# MCU.net
KiCad netlist of a schematic drawn in Altium Designer
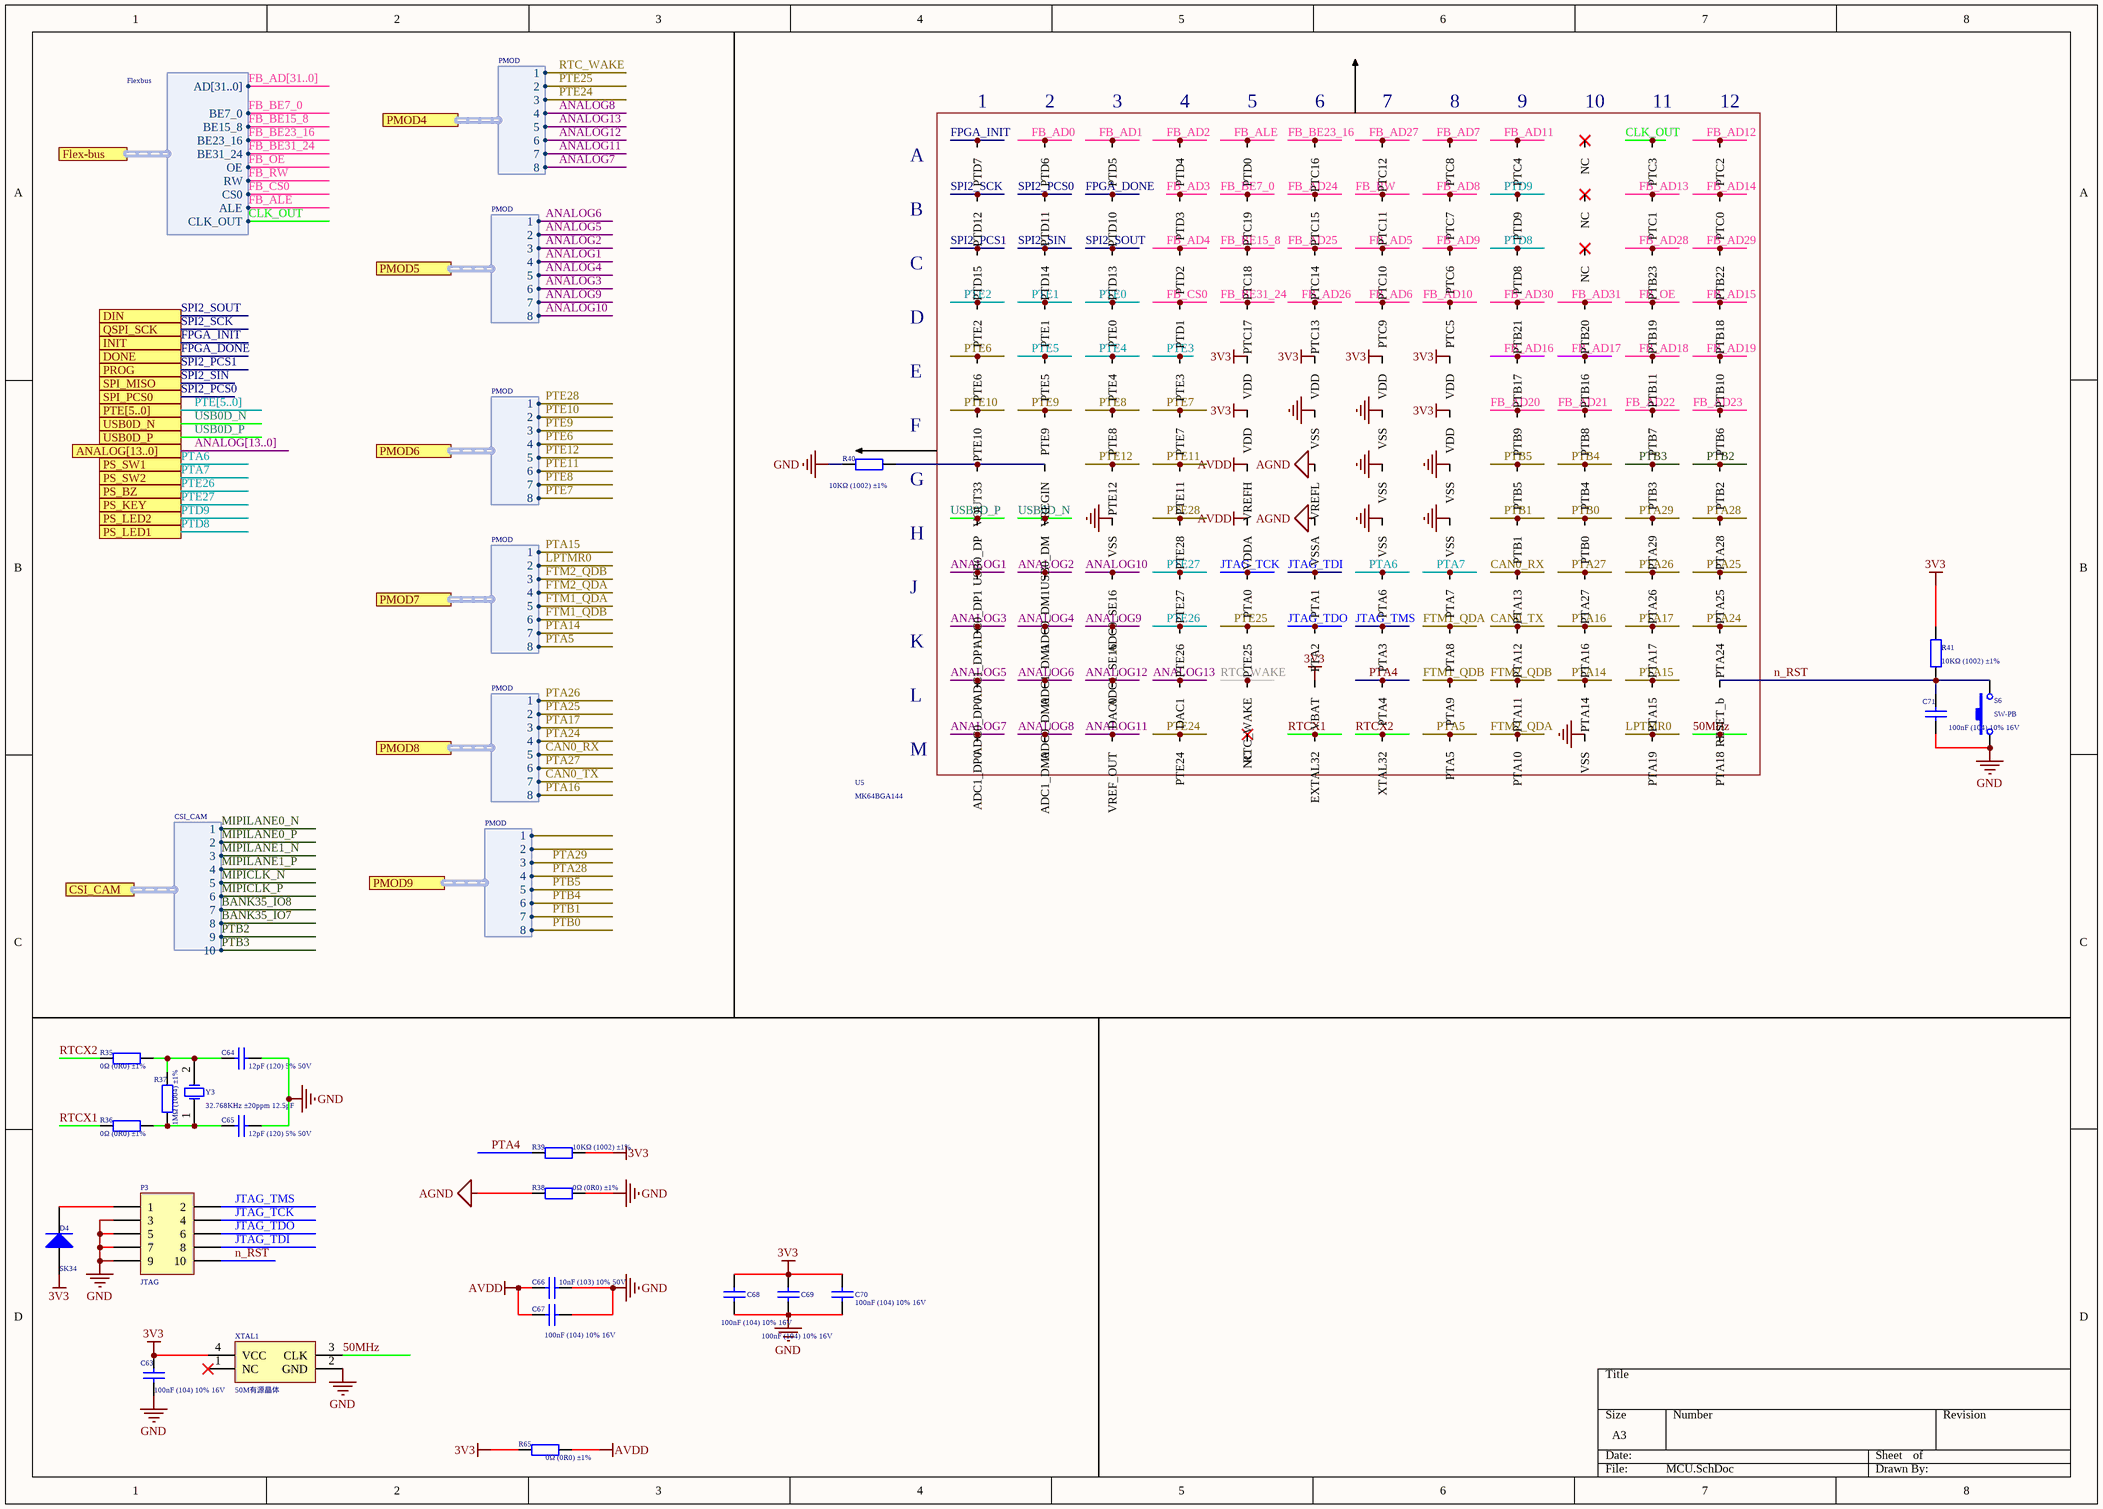
[diagram p0: MCU.SchDoc]

(export (version "E")
  (design (tool "Eeschema 10.0.6"))
  (components
    (comp (ref "C63")
      (value "100nF (104) 10% 16V")
      (footprint "0402_C")
      (description "贴片电容")
      (libsource (lib "Cap") (part "0402 100nF (104) 10% 16V"))
    )
    (comp (ref "C64")
      (value "12pF (120) 5% 50V")
      (footprint "0402_C")
      (description "贴片电容")
      (libsource (lib "Cap") (part "0402 12pF (120) 5% 50V"))
    )
    (comp (ref "C65")
      (value "12pF (120) 5% 50V")
      (footprint "0402_C")
      (description "贴片电容")
      (libsource (lib "Cap") (part "0402 12pF (120) 5% 50V"))
    )
    (comp (ref "C66")
      (value "10nF (103) 10% 50V")
      (footprint "0402_C")
      (description "贴片电容")
      (libsource (lib "Cap") (part "0402 10nF (103) 10% 50V"))
    )
    (comp (ref "C67")
      (value "100nF (104) 10% 16V")
      (footprint "0402_C")
      (description "贴片电容")
      (libsource (lib "Cap") (part "0402 100nF (104) 10% 16V"))
    )
    (comp (ref "C68")
      (value "100nF (104) 10% 16V")
      (footprint "0402_C")
      (description "贴片电容")
      (libsource (lib "Cap") (part "0402 100nF (104) 10% 16V"))
    )
    (comp (ref "C69")
      (value "100nF (104) 10% 16V")
      (footprint "0402_C")
      (description "贴片电容")
      (libsource (lib "Cap") (part "0402 100nF (104) 10% 16V"))
    )
    (comp (ref "C70")
      (value "100nF (104) 10% 16V")
      (footprint "0402_C")
      (description "贴片电容")
      (libsource (lib "Cap") (part "0402 100nF (104) 10% 16V"))
    )
    (comp (ref "C71")
      (value "100nF (104) 10% 16V")
      (footprint "0402_C")
      (description "贴片电容")
      (libsource (lib "Cap") (part "0402 100nF (104) 10% 16V"))
    )
    (comp (ref "D4")
      (value "SK34")
      (footprint "C2012")
      (description "High Conductance Fast Diode")
      (fields (field (name "PUBLISHER") "Altium Limited"))
      (libsource (lib "K60-V4.0") (part "Diode 1N4148"))
    )
    (comp (ref "P3")
      (value "JTAG")
      (footprint "HDR2X5")
      (description "Header, 5-Pin, Dual row")
      (fields (field (name "PUBLISHER") "Altium Limited"))
      (libsource (lib "Sparks") (part "Header 5X2"))
    )
    (comp (ref "R35")
      (value "0Ω (0R0) ±1%")
      (footprint "0402_R")
      (description "贴片电阻")
      (libsource (lib "RES") (part "0402 0Ω (0R0) 1%"))
    )
    (comp (ref "R36")
      (value "0Ω (0R0) ±1%")
      (footprint "0402_R")
      (description "贴片电阻")
      (libsource (lib "RES") (part "0402 0Ω (0R0) 1%"))
    )
    (comp (ref "R37")
      (value "1MΩ (1004) ±1%")
      (footprint "0402_R")
      (description "贴片电阻")
      (libsource (lib "RES") (part "0402 1MΩ (1004) 1%"))
    )
    (comp (ref "R38")
      (value "0Ω (0R0) ±1%")
      (footprint "0402_R")
      (description "贴片电阻")
      (libsource (lib "RES") (part "0402 0Ω (0R0) 1%"))
    )
    (comp (ref "R39")
      (value "10KΩ (1002) ±1%")
      (footprint "0402_R")
      (description "贴片电阻")
      (libsource (lib "") (part "0402 10KΩ (1002) 1%_1"))
    )
    (comp (ref "R40")
      (value "10KΩ (1002) ±1%")
      (footprint "0402_R")
      (description "贴片电阻")
      (libsource (lib "") (part "0402 10KΩ (1002) 1%_1"))
    )
    (comp (ref "R41")
      (value "10KΩ (1002) ±1%")
      (footprint "0402_R")
      (description "贴片电阻")
      (libsource (lib "RES") (part "0402 10KΩ (1002) 1%"))
    )
    (comp (ref "R65")
      (value "0Ω (0R0) ±1%")
      (footprint "0402_R")
      (description "贴片电阻")
      (libsource (lib "Miscellaneous Devices LC") (part "0402 0Ω (0R0) 1%"))
    )
    (comp (ref "S6")
      (value "SW-PB")
      (footprint "key 3*4*2")
      (description "Switch")
      (libsource (lib "K60-V4.0") (part "SW-PB"))
    )
    (comp (ref "U5")
      (value "MK64BGA144")
      (footprint "BGA144C100P12X12_1300X1300X161")
      (libsource (lib "2号库") (part "MK64BGA144"))
    )
    (comp (ref "XTAL1") (value "50M有源晶体") (footprint "XTAL7_3225") (libsource (lib "Sparks") (part "有源晶体")))
    (comp (ref "Y3")
      (value "32.768KHz ±20ppm 12.5pF")
      (footprint "SMD-3215_2P FC - 135")
      (description "贴片晶振")
      (libsource (lib "CrystalOscillator") (part "SMD-3215_2P 32.768KHz 20ppm 12.5pF"))
    )
  )
  (nets
    (net (code "5") (name "/50MHz") (class "Default")
      (node (ref "U5") (pin "M12") (pinfunction "PTA18_M12") (pintype "passive"))
      (node (ref "XTAL1") (pin "3") (pinfunction "CLK_3") (pintype "passive"))
    )
    (net (code "6") (name "/ANALOG1") (class "Default")
      (node (ref "U5") (pin "J1") (pinfunction "ADC0_DP1_J1") (pintype "passive"))
    )
    (net (code "7") (name "/ANALOG2") (class "Default")
      (node (ref "U5") (pin "J2") (pinfunction "ADC0_DM1_J2") (pintype "passive"))
    )
    (net (code "8") (name "/ANALOG3") (class "Default")
      (node (ref "U5") (pin "K1") (pinfunction "ADC1_DP1_K1") (pintype "passive"))
    )
    (net (code "9") (name "/ANALOG4") (class "Default")
      (node (ref "U5") (pin "K2") (pinfunction "ADC1_DM1_K2") (pintype "passive"))
    )
    (net (code "10") (name "/ANALOG5") (class "Default")
      (node (ref "U5") (pin "L1") (pinfunction "ADC0_DP0_L1") (pintype "passive"))
    )
    (net (code "11") (name "/ANALOG6") (class "Default")
      (node (ref "U5") (pin "L2") (pinfunction "ADC0_DM0_L2") (pintype "passive"))
    )
    (net (code "12") (name "/ANALOG7") (class "Default")
      (node (ref "U5") (pin "M1") (pinfunction "ADC1_DP0_M1") (pintype "passive"))
    )
    (net (code "13") (name "/ANALOG8") (class "Default")
      (node (ref "U5") (pin "M2") (pinfunction "ADC1_DM0_M2") (pintype "passive"))
    )
    (net (code "14") (name "/ANALOG9") (class "Default")
      (node (ref "U5") (pin "K3") (pinfunction "ADC1_SE16_K3") (pintype "passive"))
    )
    (net (code "15") (name "/ANALOG10") (class "Default")
      (node (ref "U5") (pin "J3") (pinfunction "ADC0_SE16_J3") (pintype "passive"))
    )
    (net (code "16") (name "/ANALOG11") (class "Default")
      (node (ref "U5") (pin "M3") (pinfunction "VREF_OUT_M3") (pintype "passive"))
    )
    (net (code "17") (name "/ANALOG12") (class "Default")
      (node (ref "U5") (pin "L3") (pinfunction "DAC0_L3") (pintype "passive"))
    )
    (net (code "18") (name "/ANALOG13") (class "Default")
      (node (ref "U5") (pin "L4") (pinfunction "DAC1_L4") (pintype "passive"))
    )
    (net (code "22") (name "/CAN0_RX") (class "Default")
      (node (ref "U5") (pin "J9") (pinfunction "PTA13_J9") (pintype "passive"))
    )
    (net (code "23") (name "/CAN0_TX") (class "Default")
      (node (ref "U5") (pin "K9") (pinfunction "PTA12_K9") (pintype "passive"))
    )
    (net (code "24") (name "/CLK_OUT") (class "Default")
      (node (ref "U5") (pin "A11") (pinfunction "PTC3_A11") (pintype "passive"))
    )
    (net (code "25") (name "/FB_AD0") (class "Default")
      (node (ref "U5") (pin "A2") (pinfunction "PTD6_A2") (pintype "passive"))
    )
    (net (code "26") (name "/FB_AD1") (class "Default")
      (node (ref "U5") (pin "A3") (pinfunction "PTD5_A3") (pintype "passive"))
    )
    (net (code "27") (name "/FB_AD2") (class "Default")
      (node (ref "U5") (pin "A4") (pinfunction "PTD4_A4") (pintype "passive"))
    )
    (net (code "28") (name "/FB_AD3") (class "Default")
      (node (ref "U5") (pin "B4") (pinfunction "PTD3_B4") (pintype "passive"))
    )
    (net (code "29") (name "/FB_AD4") (class "Default")
      (node (ref "U5") (pin "C4") (pinfunction "PTD2_C4") (pintype "passive"))
    )
    (net (code "30") (name "/FB_AD5") (class "Default")
      (node (ref "U5") (pin "C7") (pinfunction "PTC10_C7") (pintype "passive"))
    )
    (net (code "31") (name "/FB_AD6") (class "Default")
      (node (ref "U5") (pin "D7") (pinfunction "PTC9_D7") (pintype "passive"))
    )
    (net (code "32") (name "/FB_AD7") (class "Default")
      (node (ref "U5") (pin "A8") (pinfunction "PTC8_A8") (pintype "passive"))
    )
    (net (code "33") (name "/FB_AD8") (class "Default")
      (node (ref "U5") (pin "B8") (pinfunction "PTC7_B8") (pintype "passive"))
    )
    (net (code "34") (name "/FB_AD9") (class "Default")
      (node (ref "U5") (pin "C8") (pinfunction "PTC6_C8") (pintype "passive"))
    )
    (net (code "35") (name "/FB_AD10") (class "Default")
      (node (ref "U5") (pin "D8") (pinfunction "PTC5_D8") (pintype "passive"))
    )
    (net (code "36") (name "/FB_AD11") (class "Default")
      (node (ref "U5") (pin "A9") (pinfunction "PTC4_A9") (pintype "passive"))
    )
    (net (code "37") (name "/FB_AD12") (class "Default")
      (node (ref "U5") (pin "A12") (pinfunction "PTC2_A12") (pintype "passive"))
    )
    (net (code "38") (name "/FB_AD13") (class "Default")
      (node (ref "U5") (pin "B11") (pinfunction "PTC1_B11") (pintype "passive"))
    )
    (net (code "39") (name "/FB_AD14") (class "Default")
      (node (ref "U5") (pin "B12") (pinfunction "PTC0_B12") (pintype "passive"))
    )
    (net (code "40") (name "/FB_AD15") (class "Default")
      (node (ref "U5") (pin "D12") (pinfunction "PTB18_D12") (pintype "passive"))
    )
    (net (code "41") (name "/FB_AD16") (class "Default")
      (node (ref "U5") (pin "E9") (pinfunction "PTB17_E9") (pintype "passive"))
    )
    (net (code "42") (name "/FB_AD17") (class "Default")
      (node (ref "U5") (pin "E10") (pinfunction "PTB16_E10") (pintype "passive"))
    )
    (net (code "43") (name "/FB_AD18") (class "Default")
      (node (ref "U5") (pin "E11") (pinfunction "PTB11_E11") (pintype "passive"))
    )
    (net (code "44") (name "/FB_AD19") (class "Default")
      (node (ref "U5") (pin "E12") (pinfunction "PTB10_E12") (pintype "passive"))
    )
    (net (code "45") (name "/FB_AD20") (class "Default")
      (node (ref "U5") (pin "F9") (pinfunction "PTB9_F9") (pintype "passive"))
    )
    (net (code "46") (name "/FB_AD21") (class "Default")
      (node (ref "U5") (pin "F10") (pinfunction "PTB8_F10") (pintype "passive"))
    )
    (net (code "47") (name "/FB_AD22") (class "Default")
      (node (ref "U5") (pin "F11") (pinfunction "PTB7_F11") (pintype "passive"))
    )
    (net (code "48") (name "/FB_AD23") (class "Default")
      (node (ref "U5") (pin "F12") (pinfunction "PTB6_F12") (pintype "passive"))
    )
    (net (code "49") (name "/FB_AD24") (class "Default")
      (node (ref "U5") (pin "B6") (pinfunction "PTC15_B6") (pintype "passive"))
    )
    (net (code "50") (name "/FB_AD25") (class "Default")
      (node (ref "U5") (pin "C6") (pinfunction "PTC14_C6") (pintype "passive"))
    )
    (net (code "51") (name "/FB_AD26") (class "Default")
      (node (ref "U5") (pin "D6") (pinfunction "PTC13_D6") (pintype "passive"))
    )
    (net (code "52") (name "/FB_AD27") (class "Default")
      (node (ref "U5") (pin "A7") (pinfunction "PTC12_A7") (pintype "passive"))
    )
    (net (code "53") (name "/FB_AD28") (class "Default")
      (node (ref "U5") (pin "C11") (pinfunction "PTB23_C11") (pintype "passive"))
    )
    (net (code "54") (name "/FB_AD29") (class "Default")
      (node (ref "U5") (pin "C12") (pinfunction "PTB22_C12") (pintype "passive"))
    )
    (net (code "55") (name "/FB_AD30") (class "Default")
      (node (ref "U5") (pin "D9") (pinfunction "PTB21_D9") (pintype "passive"))
    )
    (net (code "56") (name "/FB_AD31") (class "Default")
      (node (ref "U5") (pin "D10") (pinfunction "PTB20_D10") (pintype "passive"))
    )
    (net (code "58") (name "/FB_ALE") (class "Default")
      (node (ref "U5") (pin "A5") (pinfunction "PTD0_A5") (pintype "passive"))
    )
    (net (code "59") (name "/FB_BE7_0") (class "Default")
      (node (ref "U5") (pin "B5") (pinfunction "PTC19_B5") (pintype "passive"))
    )
    (net (code "60") (name "/FB_BE15_8") (class "Default")
      (node (ref "U5") (pin "C5") (pinfunction "PTC18_C5") (pintype "passive"))
    )
    (net (code "61") (name "/FB_BE23_16") (class "Default")
      (node (ref "U5") (pin "A6") (pinfunction "PTC16_A6") (pintype "passive"))
    )
    (net (code "62") (name "/FB_BE31_24") (class "Default")
      (node (ref "U5") (pin "D5") (pinfunction "PTC17_D5") (pintype "passive"))
    )
    (net (code "63") (name "/FB_CS0") (class "Default")
      (node (ref "U5") (pin "D4") (pinfunction "PTD1_D4") (pintype "passive"))
    )
    (net (code "64") (name "/FB_OE") (class "Default")
      (node (ref "U5") (pin "D11") (pinfunction "PTB19_D11") (pintype "passive"))
    )
    (net (code "65") (name "/FB_RW") (class "Default")
      (node (ref "U5") (pin "B7") (pinfunction "PTC11_B7") (pintype "passive"))
    )
    (net (code "66") (name "/FPGA_DONE") (class "Default")
      (node (ref "U5") (pin "B3") (pinfunction "PTD10_B3") (pintype "passive"))
    )
    (net (code "67") (name "/FPGA_INIT") (class "Default")
      (node (ref "U5") (pin "A1") (pinfunction "PTD7_A1") (pintype "passive"))
    )
    (net (code "68") (name "/FTM1_QDA") (class "Default")
      (node (ref "U5") (pin "K8") (pinfunction "PTA8_K8") (pintype "passive"))
    )
    (net (code "69") (name "/FTM1_QDB") (class "Default")
      (node (ref "U5") (pin "L8") (pinfunction "PTA9_L8") (pintype "passive"))
    )
    (net (code "70") (name "/FTM2_QDA") (class "Default")
      (node (ref "U5") (pin "M9") (pinfunction "PTA10_M9") (pintype "passive"))
    )
    (net (code "71") (name "/FTM2_QDB") (class "Default")
      (node (ref "U5") (pin "L9") (pinfunction "PTA11_L9") (pintype "passive"))
    )
    (net (code "72") (name "/JTAG_TCK") (class "Default")
      (node (ref "P3") (pin "4") (pinfunction "4_4") (pintype "passive"))
      (node (ref "U5") (pin "J5") (pinfunction "PTA0_J5") (pintype "passive"))
    )
    (net (code "73") (name "/JTAG_TDI") (class "Default")
      (node (ref "P3") (pin "8") (pinfunction "8_8") (pintype "passive"))
      (node (ref "U5") (pin "J6") (pinfunction "PTA1_J6") (pintype "passive"))
    )
    (net (code "74") (name "/JTAG_TDO") (class "Default")
      (node (ref "P3") (pin "6") (pinfunction "6_6") (pintype "passive"))
      (node (ref "U5") (pin "K6") (pinfunction "PTA2_K6") (pintype "passive"))
    )
    (net (code "75") (name "/JTAG_TMS") (class "Default")
      (node (ref "P3") (pin "2") (pinfunction "2_2") (pintype "passive"))
      (node (ref "U5") (pin "K7") (pinfunction "PTA3_K7") (pintype "passive"))
    )
    (net (code "76") (name "/LPTMR0") (class "Default")
      (node (ref "U5") (pin "M11") (pinfunction "PTA19_M11") (pintype "passive"))
    )
    (net (code "83") (name "/PTA4") (class "Default")
      (node (ref "R39") (pin "1") (pinfunction "1_1") (pintype "passive"))
      (node (ref "U5") (pin "L7") (pinfunction "PTA4_L7") (pintype "passive"))
    )
    (net (code "84") (name "/PTA5") (class "Default")
      (node (ref "U5") (pin "M8") (pinfunction "PTA5_M8") (pintype "passive"))
    )
    (net (code "85") (name "/PTA6") (class "Default")
      (node (ref "U5") (pin "J7") (pinfunction "PTA6_J7") (pintype "passive"))
    )
    (net (code "86") (name "/PTA7") (class "Default")
      (node (ref "U5") (pin "J8") (pinfunction "PTA7_J8") (pintype "passive"))
    )
    (net (code "87") (name "/PTA14") (class "Default")
      (node (ref "U5") (pin "L10") (pinfunction "PTA14_L10") (pintype "passive"))
    )
    (net (code "88") (name "/PTA15") (class "Default")
      (node (ref "U5") (pin "L11") (pinfunction "PTA15_L11") (pintype "passive"))
    )
    (net (code "89") (name "/PTA16") (class "Default")
      (node (ref "U5") (pin "K10") (pinfunction "PTA16_K10") (pintype "passive"))
    )
    (net (code "90") (name "/PTA17") (class "Default")
      (node (ref "U5") (pin "K11") (pinfunction "PTA17_K11") (pintype "passive"))
    )
    (net (code "91") (name "/PTA24") (class "Default")
      (node (ref "U5") (pin "K12") (pinfunction "PTA24_K12") (pintype "passive"))
    )
    (net (code "92") (name "/PTA25") (class "Default")
      (node (ref "U5") (pin "J12") (pinfunction "PTA25_J12") (pintype "passive"))
    )
    (net (code "93") (name "/PTA26") (class "Default")
      (node (ref "U5") (pin "J11") (pinfunction "PTA26_J11") (pintype "passive"))
    )
    (net (code "94") (name "/PTA27") (class "Default")
      (node (ref "U5") (pin "J10") (pinfunction "PTA27_J10") (pintype "passive"))
    )
    (net (code "95") (name "/PTA28") (class "Default")
      (node (ref "U5") (pin "H12") (pinfunction "PTA28_H12") (pintype "passive"))
    )
    (net (code "96") (name "/PTA29") (class "Default")
      (node (ref "U5") (pin "H11") (pinfunction "PTA29_H11") (pintype "passive"))
    )
    (net (code "97") (name "/PTB0") (class "Default")
      (node (ref "U5") (pin "H10") (pinfunction "PTB0_H10") (pintype "passive"))
    )
    (net (code "98") (name "/PTB1") (class "Default")
      (node (ref "U5") (pin "H9") (pinfunction "PTB1_H9") (pintype "passive"))
    )
    (net (code "99") (name "/PTB2") (class "Default")
      (node (ref "U5") (pin "G12") (pinfunction "PTB2_G12") (pintype "passive"))
    )
    (net (code "100") (name "/PTB3") (class "Default")
      (node (ref "U5") (pin "G11") (pinfunction "PTB3_G11") (pintype "passive"))
    )
    (net (code "101") (name "/PTB4") (class "Default")
      (node (ref "U5") (pin "G10") (pinfunction "PTB4_G10") (pintype "passive"))
    )
    (net (code "102") (name "/PTB5") (class "Default")
      (node (ref "U5") (pin "G9") (pinfunction "PTB5_G9") (pintype "passive"))
    )
    (net (code "103") (name "/PTD8") (class "Default")
      (node (ref "U5") (pin "C9") (pinfunction "PTD8_C9") (pintype "passive"))
    )
    (net (code "104") (name "/PTD9") (class "Default")
      (node (ref "U5") (pin "B9") (pinfunction "PTD9_B9") (pintype "passive"))
    )
    (net (code "105") (name "/PTE0") (class "Default")
      (node (ref "U5") (pin "D3") (pinfunction "PTE0_D3") (pintype "passive"))
    )
    (net (code "106") (name "/PTE1") (class "Default")
      (node (ref "U5") (pin "D2") (pinfunction "PTE1_D2") (pintype "passive"))
    )
    (net (code "107") (name "/PTE2") (class "Default")
      (node (ref "U5") (pin "D1") (pinfunction "PTE2_D1") (pintype "passive"))
    )
    (net (code "108") (name "/PTE3") (class "Default")
      (node (ref "U5") (pin "E4") (pinfunction "PTE3_E4") (pintype "passive"))
    )
    (net (code "109") (name "/PTE4") (class "Default")
      (node (ref "U5") (pin "E3") (pinfunction "PTE4_E3") (pintype "passive"))
    )
    (net (code "110") (name "/PTE5") (class "Default")
      (node (ref "U5") (pin "E2") (pinfunction "PTE5_E2") (pintype "passive"))
    )
    (net (code "111") (name "/PTE6") (class "Default")
      (node (ref "U5") (pin "E1") (pinfunction "PTE6_E1") (pintype "passive"))
    )
    (net (code "112") (name "/PTE7") (class "Default")
      (node (ref "U5") (pin "F4") (pinfunction "PTE7_F4") (pintype "passive"))
    )
    (net (code "113") (name "/PTE8") (class "Default")
      (node (ref "U5") (pin "F3") (pinfunction "PTE8_F3") (pintype "passive"))
    )
    (net (code "114") (name "/PTE9") (class "Default")
      (node (ref "U5") (pin "F2") (pinfunction "PTE9_F2") (pintype "passive"))
    )
    (net (code "115") (name "/PTE10") (class "Default")
      (node (ref "U5") (pin "F1") (pinfunction "PTE10_F1") (pintype "passive"))
    )
    (net (code "116") (name "/PTE11") (class "Default")
      (node (ref "U5") (pin "G4") (pinfunction "PTE11_G4") (pintype "passive"))
    )
    (net (code "117") (name "/PTE12") (class "Default")
      (node (ref "U5") (pin "G3") (pinfunction "PTE12_G3") (pintype "passive"))
    )
    (net (code "118") (name "/PTE24") (class "Default")
      (node (ref "U5") (pin "M4") (pinfunction "PTE24_M4") (pintype "passive"))
    )
    (net (code "119") (name "/PTE25") (class "Default")
      (node (ref "U5") (pin "K5") (pinfunction "PTE25_K5") (pintype "passive"))
    )
    (net (code "120") (name "/PTE26") (class "Default")
      (node (ref "U5") (pin "K4") (pinfunction "PTE26_K4") (pintype "passive"))
    )
    (net (code "121") (name "/PTE27") (class "Default")
      (node (ref "U5") (pin "J4") (pinfunction "PTE27_J4") (pintype "passive"))
    )
    (net (code "122") (name "/PTE28") (class "Default")
      (node (ref "U5") (pin "H4") (pinfunction "PTE28_H4") (pintype "passive"))
    )
    (net (code "124") (name "/RTCX1") (class "Default")
      (node (ref "R36") (pin "1") (pinfunction "1_1") (pintype "passive"))
      (node (ref "U5") (pin "M6") (pinfunction "EXTAL32_M6") (pintype "passive"))
    )
    (net (code "125") (name "/RTCX2") (class "Default")
      (node (ref "R35") (pin "1") (pinfunction "1_1") (pintype "passive"))
      (node (ref "U5") (pin "M7") (pinfunction "XTAL32_M7") (pintype "passive"))
    )
    (net (code "126") (name "/RTC_WAKE") (class "Default")
      (node (ref "U5") (pin "L5") (pinfunction "RTC_WAKE_L5") (pintype "passive"))
    )
    (net (code "127") (name "/SPI2_PCS0") (class "Default")
      (node (ref "U5") (pin "B2") (pinfunction "PTD11_B2") (pintype "passive"))
    )
    (net (code "128") (name "/SPI2_PCS1") (class "Default")
      (node (ref "U5") (pin "C1") (pinfunction "PTD15_C1") (pintype "passive"))
    )
    (net (code "129") (name "/SPI2_SCK") (class "Default")
      (node (ref "U5") (pin "B1") (pinfunction "PTD12_B1") (pintype "passive"))
    )
    (net (code "130") (name "/SPI2_SIN") (class "Default")
      (node (ref "U5") (pin "C2") (pinfunction "PTD14_C2") (pintype "passive"))
    )
    (net (code "131") (name "/SPI2_SOUT") (class "Default")
      (node (ref "U5") (pin "C3") (pinfunction "PTD13_C3") (pintype "passive"))
    )
    (net (code "132") (name "/USB0D_N") (class "Default")
      (node (ref "U5") (pin "H2") (pinfunction "USB0_DM_H2") (pintype "passive"))
    )
    (net (code "133") (name "/USB0D_P") (class "Default")
      (node (ref "U5") (pin "H1") (pinfunction "USB0_DP_H1") (pintype "passive"))
    )
    (net (code "134") (name "/n_RST") (class "Default")
      (node (ref "C71") (pin "2") (pinfunction "2_2") (pintype "passive"))
      (node (ref "P3") (pin "10") (pinfunction "10_10") (pintype "passive"))
      (node (ref "R41") (pin "1") (pinfunction "1_1") (pintype "passive"))
      (node (ref "S6") (pin "2") (pinfunction "2_2") (pintype "passive"))
      (node (ref "U5") (pin "L12") (pinfunction "RESET_b_L12") (pintype "passive"))
    )
    (net (code "138") (name "3V3") (class "Default")
      (node (ref "C63") (pin "2") (pinfunction "2_2") (pintype "passive"))
      (node (ref "C68") (pin "2") (pinfunction "2_2") (pintype "passive"))
      (node (ref "C69") (pin "2") (pinfunction "2_2") (pintype "passive"))
      (node (ref "C70") (pin "2") (pinfunction "2_2") (pintype "passive"))
      (node (ref "D4") (pin "1") (pinfunction "A_1") (pintype "passive"))
      (node (ref "R39") (pin "2") (pinfunction "2_2") (pintype "passive"))
      (node (ref "R41") (pin "2") (pinfunction "2_2") (pintype "passive"))
      (node (ref "R65") (pin "1") (pinfunction "1_1") (pintype "passive"))
      (node (ref "U5") (pin "E5") (pinfunction "VDD_E5") (pintype "passive"))
      (node (ref "U5") (pin "E6") (pinfunction "VDD_E6") (pintype "passive"))
      (node (ref "U5") (pin "E7") (pinfunction "VDD_E7") (pintype "passive"))
      (node (ref "U5") (pin "E8") (pinfunction "VDD_E8") (pintype "passive"))
      (node (ref "U5") (pin "F5") (pinfunction "VDD_F5") (pintype "passive"))
      (node (ref "U5") (pin "F8") (pinfunction "VDD_F8") (pintype "passive"))
      (node (ref "U5") (pin "L6") (pinfunction "VBAT_L6") (pintype "passive"))
      (node (ref "XTAL1") (pin "4") (pinfunction "VCC_4") (pintype "passive"))
    )
    (net (code "139") (name "AGND") (class "Default")
      (node (ref "R38") (pin "1") (pinfunction "1_1") (pintype "passive"))
      (node (ref "U5") (pin "G6") (pinfunction "VREFL_G6") (pintype "passive"))
      (node (ref "U5") (pin "H6") (pinfunction "VSSA_H6") (pintype "passive"))
    )
    (net (code "140") (name "AVDD") (class "Default")
      (node (ref "C66") (pin "1") (pinfunction "1_1") (pintype "passive"))
      (node (ref "C67") (pin "1") (pinfunction "1_1") (pintype "passive"))
      (node (ref "R65") (pin "2") (pinfunction "2_2") (pintype "passive"))
      (node (ref "U5") (pin "G5") (pinfunction "VREFH_G5") (pintype "passive"))
      (node (ref "U5") (pin "H5") (pinfunction "VDDA_H5") (pintype "passive"))
    )
    (net (code "141") (name "GND") (class "Default")
      (node (ref "C63") (pin "1") (pinfunction "1_1") (pintype "passive"))
      (node (ref "C64") (pin "2") (pinfunction "2_2") (pintype "passive"))
      (node (ref "C65") (pin "2") (pinfunction "2_2") (pintype "passive"))
      (node (ref "C66") (pin "2") (pinfunction "2_2") (pintype "passive"))
      (node (ref "C67") (pin "2") (pinfunction "2_2") (pintype "passive"))
      (node (ref "C68") (pin "1") (pinfunction "1_1") (pintype "passive"))
      (node (ref "C69") (pin "1") (pinfunction "1_1") (pintype "passive"))
      (node (ref "C70") (pin "1") (pinfunction "1_1") (pintype "passive"))
      (node (ref "C71") (pin "1") (pinfunction "1_1") (pintype "passive"))
      (node (ref "P3") (pin "3") (pinfunction "3_3") (pintype "passive"))
      (node (ref "P3") (pin "5") (pinfunction "5_5") (pintype "passive"))
      (node (ref "P3") (pin "7") (pinfunction "7_7") (pintype "passive"))
      (node (ref "P3") (pin "9") (pinfunction "9_9") (pintype "passive"))
      (node (ref "R38") (pin "2") (pinfunction "2_2") (pintype "passive"))
      (node (ref "R40") (pin "1") (pinfunction "1_1") (pintype "passive"))
      (node (ref "S6") (pin "1") (pinfunction "1_1") (pintype "passive"))
      (node (ref "U5") (pin "F6") (pinfunction "VSS_F6") (pintype "passive"))
      (node (ref "U5") (pin "F7") (pinfunction "VSS_F7") (pintype "passive"))
      (node (ref "U5") (pin "G7") (pinfunction "VSS_G7") (pintype "passive"))
      (node (ref "U5") (pin "G8") (pinfunction "VSS_G8") (pintype "passive"))
      (node (ref "U5") (pin "H3") (pinfunction "VSS_H3") (pintype "passive"))
      (node (ref "U5") (pin "H7") (pinfunction "VSS_H7") (pintype "passive"))
      (node (ref "U5") (pin "H8") (pinfunction "VSS_H8") (pintype "passive"))
      (node (ref "U5") (pin "M10") (pinfunction "VSS_M10") (pintype "passive"))
      (node (ref "XTAL1") (pin "2") (pinfunction "GND_2") (pintype "passive"))
    )
    (net (code "142") (name "Net-(D4-K)") (class "Default")
      (node (ref "D4") (pin "2") (pinfunction "K_2") (pintype "passive"))
      (node (ref "P3") (pin "1") (pinfunction "1_1") (pintype "passive"))
    )
    (net (code "143") (name "Net-(U5-VOUT33)") (class "Default")
      (node (ref "R40") (pin "2") (pinfunction "2_2") (pintype "passive"))
      (node (ref "U5") (pin "G1") (pinfunction "VOUT33_G1") (pintype "passive"))
      (node (ref "U5") (pin "G2") (pinfunction "VREGIN_G2") (pintype "passive"))
    )
    (net (code "144") (name "Net-(Y3-OSC1)") (class "Default")
      (node (ref "C65") (pin "1") (pinfunction "1_1") (pintype "passive"))
      (node (ref "R36") (pin "2") (pinfunction "2_2") (pintype "passive"))
      (node (ref "R37") (pin "1") (pinfunction "1_1") (pintype "passive"))
      (node (ref "Y3") (pin "1") (pinfunction "OSC1_1") (pintype "passive"))
    )
    (net (code "145") (name "Net-(Y3-OSC2)") (class "Default")
      (node (ref "C64") (pin "1") (pinfunction "1_1") (pintype "passive"))
      (node (ref "R35") (pin "2") (pinfunction "2_2") (pintype "passive"))
      (node (ref "R37") (pin "2") (pinfunction "2_2") (pintype "passive"))
      (node (ref "Y3") (pin "2") (pinfunction "OSC2_2") (pintype "passive"))
    )
    (net (code "146") (name "unconnected-(U5-NC-PadA10)") (class "Default")
      (node (ref "U5") (pin "A10") (pinfunction "NC_A10") (pintype "passive+no_connect"))
    )
    (net (code "147") (name "unconnected-(U5-NC-PadB10)") (class "Default")
      (node (ref "U5") (pin "B10") (pinfunction "NC_B10") (pintype "passive+no_connect"))
    )
    (net (code "148") (name "unconnected-(U5-NC-PadC10)") (class "Default")
      (node (ref "U5") (pin "C10") (pinfunction "NC_C10") (pintype "passive+no_connect"))
    )
    (net (code "149") (name "unconnected-(U5-NC-PadM5)") (class "Default")
      (node (ref "U5") (pin "M5") (pinfunction "NC_M5") (pintype "passive+no_connect"))
    )
    (net (code "150") (name "unconnected-(XTAL1-NC-Pad1)") (class "Default")
      (node (ref "XTAL1") (pin "1") (pinfunction "NC_1") (pintype "passive+no_connect"))
    )
  )
)
